# Connector.net
KiCad netlist of a schematic drawn in Altium Designer
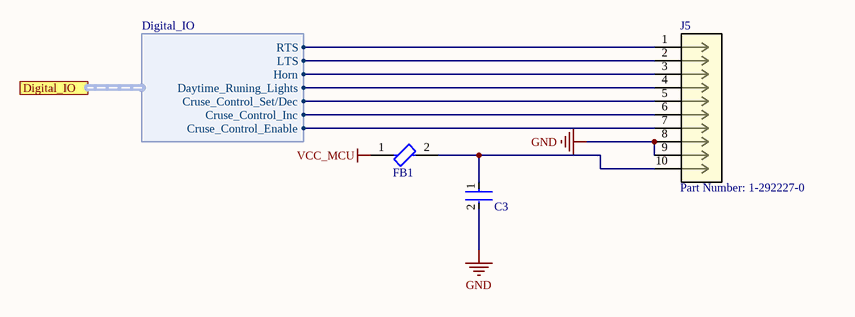
[diagram p0: Connector.SchDoc]

(export (version "E")
  (design (tool "Eeschema 10.0.6"))
  (components
    (comp (ref "C3")
      (value "C0603C104K5RACTU")
      (footprint "Kemet_C0603_IPC_A")
      (libsource (lib "UNK_Kemet_C0603C104K5RACTU_eec") (part "C0603C104K5RACTU"))
    )
    (comp (ref "FB1")
      (value "2508056017Y2")
      (footprint "Fair-Rite_250805_0")
      (libsource (lib "FBead_Fair-Rite_2508056017Y2_eec") (part "2508056017Y2"))
    )
    (comp (ref "J5")
      (value "Part Number: 1-292227-0")
      (footprint "CON10_1X10_DRH_H")
      (description "No Description Available")
      (fields
        (field (name "MANUFACTURER_PART_NUMBER") "1-292227-0")
        (field (name "COPYRIGHT") "Copyright (C) 2018 Accelerated Designs. All rights reserved")
      )
      (libsource (lib "AMP_MINI_CT_10PIN") (part "1-292227-0"))
    )
  )
  (nets
    (net (code "2") (name "/Cruse_Control_Enable") (class "Default")
      (node (ref "J5") (pin "7") (pinfunction "7_7") (pintype "passive"))
    )
    (net (code "3") (name "/Cruse_Control_Inc") (class "Default")
      (node (ref "J5") (pin "6") (pinfunction "6_6") (pintype "passive"))
    )
    (net (code "4") (name "/Cruse_Control_Set{slash}Dec") (class "Default")
      (node (ref "J5") (pin "5") (pinfunction "5_5") (pintype "passive"))
    )
    (net (code "5") (name "/Daytime_Runing_Lights") (class "Default")
      (node (ref "J5") (pin "4") (pinfunction "4_4") (pintype "passive"))
    )
    (net (code "6") (name "/Horn") (class "Default")
      (node (ref "J5") (pin "3") (pinfunction "3_3") (pintype "passive"))
    )
    (net (code "7") (name "/LTS") (class "Default")
      (node (ref "J5") (pin "2") (pinfunction "2_2") (pintype "passive"))
    )
    (net (code "8") (name "/RTS") (class "Default")
      (node (ref "J5") (pin "1") (pinfunction "1_1") (pintype "passive"))
    )
    (net (code "10") (name "GND") (class "Default")
      (node (ref "C3") (pin "2") (pinfunction "2_2") (pintype "passive"))
      (node (ref "J5") (pin "8") (pinfunction "8_8") (pintype "passive"))
      (node (ref "J5") (pin "9") (pinfunction "9_9") (pintype "passive"))
    )
    (net (code "11") (name "Net-(C3-Pad1)") (class "Default")
      (node (ref "C3") (pin "1") (pinfunction "1_1") (pintype "passive"))
      (node (ref "FB1") (pin "2") (pinfunction "2_2") (pintype "passive"))
      (node (ref "J5") (pin "10") (pinfunction "10_10") (pintype "passive"))
    )
    (net (code "12") (name "VCC_MCU") (class "Default")
      (node (ref "FB1") (pin "1") (pinfunction "1_1") (pintype "passive"))
    )
  )
)
